# keycard.net
KiCad netlist of a schematic drawn in Altium Designer
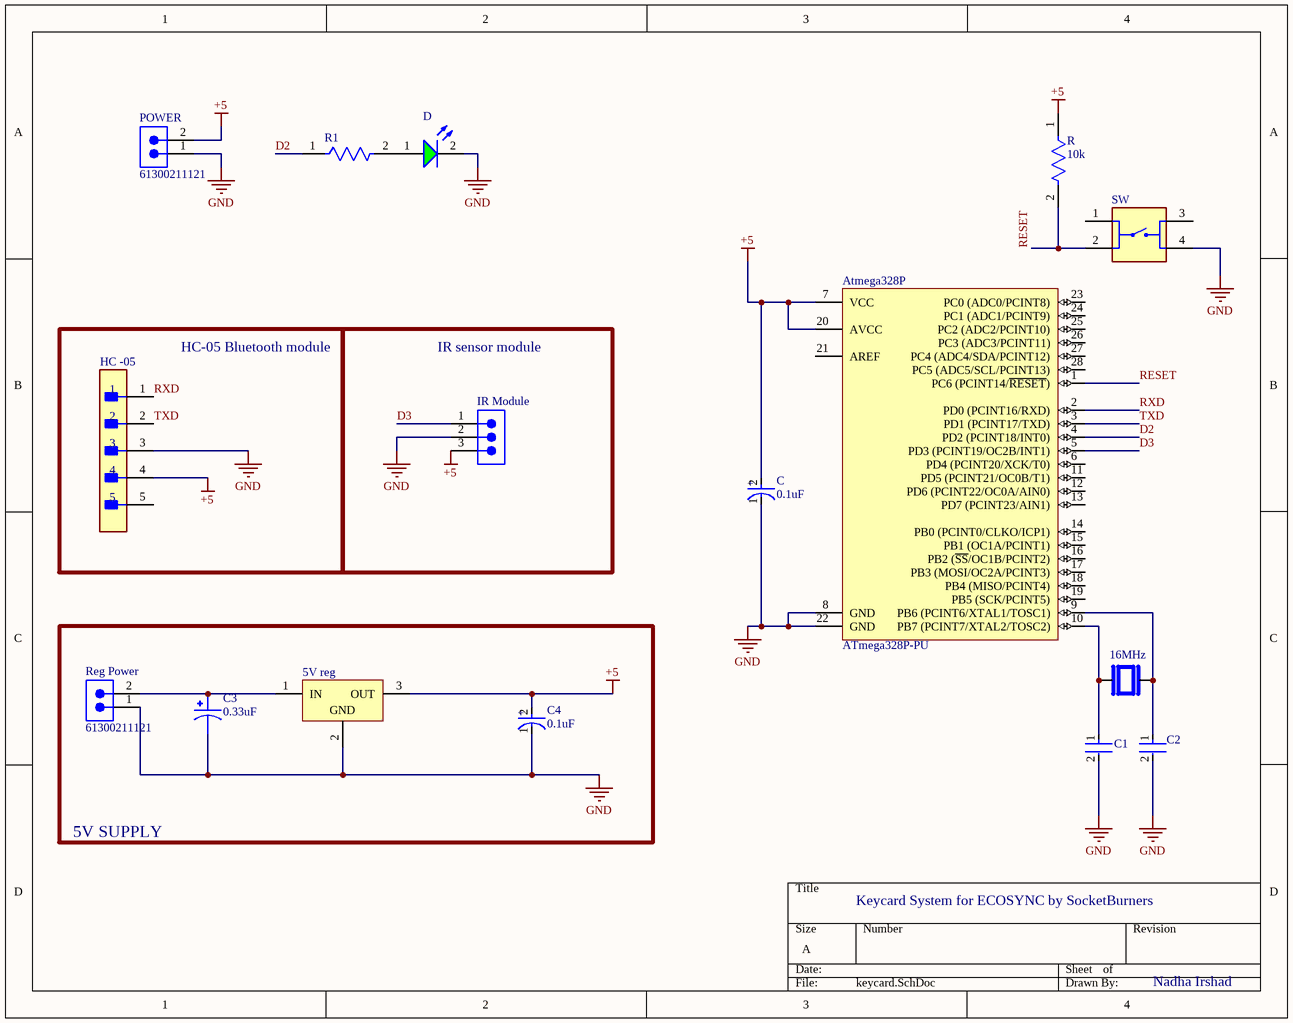
[diagram p0: keycard.SchDoc]

(export (version "E")
  (design (tool "Eeschema 10.0.6"))
  (components
    (comp (ref "5V reg")
      (value "L7805CV")
      (footprint "TO220")
      (description "Positive Voltage Regulator, 5V, 3-Pin TO-220")
      (libsource (lib "Altium Content Vault") (part "PM-REG-L4940-SIL3"))
    )
    (comp (ref "16MHz")
      (value "ABL-16.000MHZ-B2")
      (footprint "XTAL_HC49P488W46L1150T500H350")
      (description "HC/49US (AT49) MICROPROCESSOR CRYSTAL")
      (fields (field (name "MF") "Abracon"))
      (libsource (lib "ABL-16.000MHZ-B2") (part "ABL-16.000MHZ-B2"))
    )
    (comp (ref "Atmega328P")
      (value "ATmega328P-PU")
      (footprint "28P3")
      (libsource (lib "Altium Content Vault") (part "MC-8B-ATM48-IL28"))
    )
    (comp (ref "C")
      (value "0.1uF")
      (footprint "FP-RAD-TH-D_6_3_0_5-L_11-MFG")
      (description "Aluminum Electrolytic Capacitors (Radial Lead Type) 330uF ±20% 6.3V")
      (fields (field (name "TOLERANCE") "20%"))
      (libsource (lib "Altium Content Vault") (part "a00bbbee19879c290e62620ae7e47b1"))
    )
    (comp (ref "C1")
      (value "RDE5C2A220J0M1H03A")
      (footprint "FP-RDE0M1-MFG")
      (description "Ceramic Capacitor 22pF ±5% 100V C0G Radial")
      (fields (field (name "TOLERANCE") "5%"))
      (libsource (lib "Components - 02.05.24 - 16.42") (part "CMP-06035-022985-1"))
    )
    (comp (ref "C2")
      (value "RDE5C2A220J0M1H03A")
      (footprint "FP-RDE0M1-MFG")
      (description "Ceramic Capacitor 22pF ±5% 100V C0G Radial")
      (fields (field (name "TOLERANCE") "5%"))
      (libsource (lib "Components - 02.05.24 - 16.42") (part "CMP-06035-022985-1"))
    )
    (comp (ref "C3")
      (value "0.33uF")
      (footprint "CAPPRD200W50D550H1250")
      (description "CAP ALUM 0.33UF 20% 100V RADIAL")
      (fields (field (name "MP") "UVR2AR33MDD") (field (name "MF") "Nichicon"))
      (libsource (lib "UVR2AR33MDD") (part "UVR2AR33MDD"))
    )
    (comp (ref "C4")
      (value "0.1uF")
      (footprint "FP-RAD-TH-D_6_3_0_5-L_11-MFG")
      (description "Aluminum Electrolytic Capacitors (Radial Lead Type) 330uF ±20% 6.3V")
      (fields (field (name "TOLERANCE") "20%"))
      (libsource (lib "Altium Content Vault") (part "a00bbbee19879c290e62620ae7e47b1"))
    )
    (comp (ref "D")
      (value "151031VS06000")
      (footprint "WL-TMRC_D3.95H5.3")
      (libsource (lib "Altium Content Vault") (part "LED_Green_1A-2K"))
    )
    (comp (ref "HC -05")
      (value "22-28-4050")
      (footprint "FP-22-28-4050-MFG")
      (libsource (lib "Altium Content Vault") (part "bf93c07fd2649a848d0ec8585582aab"))
    )
    (comp (ref "IR Module")
      (value "61300311121")
      (footprint "61300311121")
      (libsource (lib "Altium Content Vault") (part "Header_Male_1R_03P"))
    )
    (comp (ref "POWER")
      (value "61300211121")
      (footprint "61300211121")
      (libsource (lib "Altium Content Vault") (part "Header_Male_1R_02P"))
    )
    (comp (ref "R")
      (value "10k")
      (footprint "FP-CF18-MFG")
      (description "RES 10K OHM 1/8W 5% CF AXIAL")
      (fields
        (field (name "MANUFACTURER PART NUMBER") "CF18JT10K0")
        (field (name "MANUFACTURER") "Stackpole Electronics")
      )
      (libsource (lib "Altium Content Vault") (part "1029c3af85768c4190bb7ad29bc67b5"))
    )
    (comp (ref "R1")
      (value "CF18JT10K0")
      (footprint "FP-CF18-MFG")
      (description "RES 10K OHM 1/8W 5% CF AXIAL")
      (fields
        (field (name "MANUFACTURER") "Stackpole Electronics")
        (field (name "OCTOPART") "https://octopart.com/cf18jt10k0-stackpole+electronics-19205642")
      )
      (libsource (lib "Altium Content Vault") (part "1029c3af85768c4190bb7ad29bc67b5"))
    )
    (comp (ref "Reg Power")
      (value "61300211121")
      (footprint "61300211121")
      (libsource (lib "Altium Content Vault") (part "Header_Male_1R_02P"))
    )
    (comp (ref "SW")
      (value "1825910-6")
      (footprint "SW_1825910-6-4")
      (description "Switch Push Button OFF (ON) SPST Round Button 0.05A 24VDC Momentary Contact PC Pins Thru-Hole")
      (fields (field (name "MF") "TE Connectivity") (field (name "DIGI-KEY_PART_NUMBER") "450-1650-ND"))
      (libsource (lib "1825910-6") (part "1825910-6"))
    )
  )
  (nets
    (net (code "1") (name "+5") (class "Default")
      (node (ref "5V reg") (pin "3") (pinfunction "OUT_3") (pintype "power_in"))
      (node (ref "Atmega328P") (pin "20") (pinfunction "AVCC_20") (pintype "power_in"))
      (node (ref "Atmega328P") (pin "7") (pinfunction "VCC_7") (pintype "power_in"))
      (node (ref "C") (pin "2") (pinfunction "A_2") (pintype "passive"))
      (node (ref "C4") (pin "2") (pinfunction "A_2") (pintype "passive"))
      (node (ref "HC -05") (pin "4") (pinfunction "4_4") (pintype "passive"))
      (node (ref "IR Module") (pin "3") (pinfunction "3_3") (pintype "passive"))
      (node (ref "POWER") (pin "2") (pinfunction "2_2") (pintype "passive"))
      (node (ref "R") (pin "1") (pinfunction "1_1") (pintype "passive"))
    )
    (net (code "2") (name "/D2") (class "Default")
      (node (ref "Atmega328P") (pin "4") (pinfunction "PD2_(PCINT18/INT0)_4") (pintype "bidirectional"))
      (node (ref "R1") (pin "1") (pinfunction "1_1") (pintype "passive"))
    )
    (net (code "3") (name "/D3") (class "Default")
      (node (ref "Atmega328P") (pin "5") (pinfunction "PD3_(PCINT19/OC2B/INT1)_5") (pintype "bidirectional"))
      (node (ref "IR Module") (pin "1") (pinfunction "1_1") (pintype "passive"))
    )
    (net (code "4") (name "/RESET") (class "Default")
      (node (ref "Atmega328P") (pin "1") (pinfunction "PC6_(PCINT14/~{RESET})_1") (pintype "bidirectional"))
      (node (ref "R") (pin "2") (pinfunction "2_2") (pintype "passive"))
      (node (ref "SW") (pin "2") (pinfunction "2_2") (pintype "passive"))
    )
    (net (code "5") (name "/RXD") (class "Default")
      (node (ref "Atmega328P") (pin "2") (pinfunction "PD0_(PCINT16/RXD)_2") (pintype "bidirectional"))
      (node (ref "HC -05") (pin "1") (pinfunction "1_1") (pintype "passive"))
    )
    (net (code "6") (name "/TXD") (class "Default")
      (node (ref "Atmega328P") (pin "3") (pinfunction "PD1_(PCINT17/TXD)_3") (pintype "bidirectional"))
      (node (ref "HC -05") (pin "2") (pinfunction "2_2") (pintype "passive"))
    )
    (net (code "7") (name "GND") (class "Default")
      (node (ref "5V reg") (pin "2") (pinfunction "GND_2") (pintype "power_in"))
      (node (ref "Atmega328P") (pin "22") (pinfunction "GND_22") (pintype "power_in"))
      (node (ref "Atmega328P") (pin "8") (pinfunction "GND_8") (pintype "power_in"))
      (node (ref "C") (pin "1") (pinfunction "C_1") (pintype "passive"))
      (node (ref "C1") (pin "2") (pinfunction "2_2") (pintype "passive"))
      (node (ref "C2") (pin "2") (pinfunction "2_2") (pintype "passive"))
      (node (ref "C3") (pin "2") (pinfunction "2_2") (pintype "passive"))
      (node (ref "C4") (pin "1") (pinfunction "C_1") (pintype "passive"))
      (node (ref "D") (pin "2") (pinfunction "K_2") (pintype "passive"))
      (node (ref "HC -05") (pin "3") (pinfunction "3_3") (pintype "passive"))
      (node (ref "IR Module") (pin "2") (pinfunction "2_2") (pintype "passive"))
      (node (ref "POWER") (pin "1") (pinfunction "1_1") (pintype "passive"))
      (node (ref "Reg Power") (pin "1") (pinfunction "1_1") (pintype "passive"))
      (node (ref "SW") (pin "4") (pinfunction "4_4") (pintype "passive"))
    )
    (net (code "8") (name "Net-(5V reg-IN)") (class "Default")
      (node (ref "5V reg") (pin "1") (pinfunction "IN_1") (pintype "power_in"))
      (node (ref "C3") (pin "1") (pinfunction "1_1") (pintype "passive"))
      (node (ref "Reg Power") (pin "2") (pinfunction "2_2") (pintype "passive"))
    )
    (net (code "9") (name "Net-(Atmega328P-PB6_(PCINT6{slash}XTAL1{slash}TOSC1))") (class "Default")
      (node (ref "16MHz") (pin "2") (pinfunction "2_2") (pintype "passive"))
      (node (ref "Atmega328P") (pin "9") (pinfunction "PB6_(PCINT6/XTAL1/TOSC1)_9") (pintype "bidirectional"))
      (node (ref "C2") (pin "1") (pinfunction "1_1") (pintype "passive"))
    )
    (net (code "10") (name "Net-(Atmega328P-PB7_(PCINT7{slash}XTAL2{slash}TOSC2))") (class "Default")
      (node (ref "16MHz") (pin "1") (pinfunction "1_1") (pintype "passive"))
      (node (ref "Atmega328P") (pin "10") (pinfunction "PB7_(PCINT7/XTAL2/TOSC2)_10") (pintype "bidirectional"))
      (node (ref "C1") (pin "1") (pinfunction "1_1") (pintype "passive"))
    )
    (net (code "11") (name "Net-(D-A)") (class "Default")
      (node (ref "D") (pin "1") (pinfunction "A_1") (pintype "passive"))
      (node (ref "R1") (pin "2") (pinfunction "2_2") (pintype "passive"))
    )
    (net (code "12") (name "unconnected-(Atmega328P-AREF-Pad21)") (class "Default")
      (node (ref "Atmega328P") (pin "21") (pinfunction "AREF_21") (pintype "power_in"))
    )
    (net (code "13") (name "unconnected-(Atmega328P-PB0_(PCINT0{slash}CLKO{slash}ICP1)-Pad14)") (class "Default")
      (node (ref "Atmega328P") (pin "14") (pinfunction "PB0_(PCINT0/CLKO/ICP1)_14") (pintype "bidirectional"))
    )
    (net (code "14") (name "unconnected-(Atmega328P-PB1_(OC1A{slash}PCINT1)-Pad15)") (class "Default")
      (node (ref "Atmega328P") (pin "15") (pinfunction "PB1_(OC1A/PCINT1)_15") (pintype "bidirectional"))
    )
    (net (code "15") (name "unconnected-(Atmega328P-PB2_(~{SS}{slash}OC1B{slash}PCINT2)-Pad16)") (class "Default")
      (node (ref "Atmega328P") (pin "16") (pinfunction "PB2_(~{SS}/OC1B/PCINT2)_16") (pintype "bidirectional"))
    )
    (net (code "16") (name "unconnected-(Atmega328P-PB3_(MOSI{slash}OC2A{slash}PCINT3)-Pad17)") (class "Default")
      (node (ref "Atmega328P") (pin "17") (pinfunction "PB3_(MOSI/OC2A/PCINT3)_17") (pintype "bidirectional"))
    )
    (net (code "17") (name "unconnected-(Atmega328P-PB4_(MISO{slash}PCINT4)-Pad18)") (class "Default")
      (node (ref "Atmega328P") (pin "18") (pinfunction "PB4_(MISO/PCINT4)_18") (pintype "bidirectional"))
    )
    (net (code "18") (name "unconnected-(Atmega328P-PB5_(SCK{slash}PCINT5)-Pad19)") (class "Default")
      (node (ref "Atmega328P") (pin "19") (pinfunction "PB5_(SCK/PCINT5)_19") (pintype "bidirectional"))
    )
    (net (code "19") (name "unconnected-(Atmega328P-PC0_(ADC0{slash}PCINT8)-Pad23)") (class "Default")
      (node (ref "Atmega328P") (pin "23") (pinfunction "PC0_(ADC0/PCINT8)_23") (pintype "bidirectional"))
    )
    (net (code "20") (name "unconnected-(Atmega328P-PC1_(ADC1{slash}PCINT9)-Pad24)") (class "Default")
      (node (ref "Atmega328P") (pin "24") (pinfunction "PC1_(ADC1/PCINT9)_24") (pintype "bidirectional"))
    )
    (net (code "21") (name "unconnected-(Atmega328P-PC2_(ADC2{slash}PCINT10)-Pad25)") (class "Default")
      (node (ref "Atmega328P") (pin "25") (pinfunction "PC2_(ADC2/PCINT10)_25") (pintype "bidirectional"))
    )
    (net (code "22") (name "unconnected-(Atmega328P-PC3_(ADC3{slash}PCINT11)-Pad26)") (class "Default")
      (node (ref "Atmega328P") (pin "26") (pinfunction "PC3_(ADC3/PCINT11)_26") (pintype "bidirectional"))
    )
    (net (code "23") (name "unconnected-(Atmega328P-PC4_(ADC4{slash}SDA{slash}PCINT12)-Pad27)") (class "Default")
      (node (ref "Atmega328P") (pin "27") (pinfunction "PC4_(ADC4/SDA/PCINT12)_27") (pintype "bidirectional"))
    )
    (net (code "24") (name "unconnected-(Atmega328P-PC5_(ADC5{slash}SCL{slash}PCINT13)-Pad28)") (class "Default")
      (node (ref "Atmega328P") (pin "28") (pinfunction "PC5_(ADC5/SCL/PCINT13)_28") (pintype "bidirectional"))
    )
    (net (code "25") (name "unconnected-(Atmega328P-PD4_(PCINT20{slash}XCK{slash}T0)-Pad6)") (class "Default")
      (node (ref "Atmega328P") (pin "6") (pinfunction "PD4_(PCINT20/XCK/T0)_6") (pintype "bidirectional"))
    )
    (net (code "26") (name "unconnected-(Atmega328P-PD5_(PCINT21{slash}OC0B{slash}T1)-Pad11)") (class "Default")
      (node (ref "Atmega328P") (pin "11") (pinfunction "PD5_(PCINT21/OC0B/T1)_11") (pintype "bidirectional"))
    )
    (net (code "27") (name "unconnected-(Atmega328P-PD6_(PCINT22{slash}OC0A{slash}AIN0)-Pad12)") (class "Default")
      (node (ref "Atmega328P") (pin "12") (pinfunction "PD6_(PCINT22/OC0A/AIN0)_12") (pintype "bidirectional"))
    )
    (net (code "28") (name "unconnected-(Atmega328P-PD7_(PCINT23{slash}AIN1)-Pad13)") (class "Default")
      (node (ref "Atmega328P") (pin "13") (pinfunction "PD7_(PCINT23/AIN1)_13") (pintype "bidirectional"))
    )
    (net (code "29") (name "unconnected-(HC -05-Pad5)") (class "Default")
      (node (ref "HC -05") (pin "5") (pinfunction "5_5") (pintype "passive"))
    )
    (net (code "30") (name "unconnected-(SW-Pad1)") (class "Default")
      (node (ref "SW") (pin "1") (pinfunction "1_1") (pintype "passive"))
    )
    (net (code "31") (name "unconnected-(SW-Pad3)") (class "Default")
      (node (ref "SW") (pin "3") (pinfunction "3_3") (pintype "passive"))
    )
  )
)
